# SD_Card.net
KiCad netlist of a schematic drawn in Altium Designer
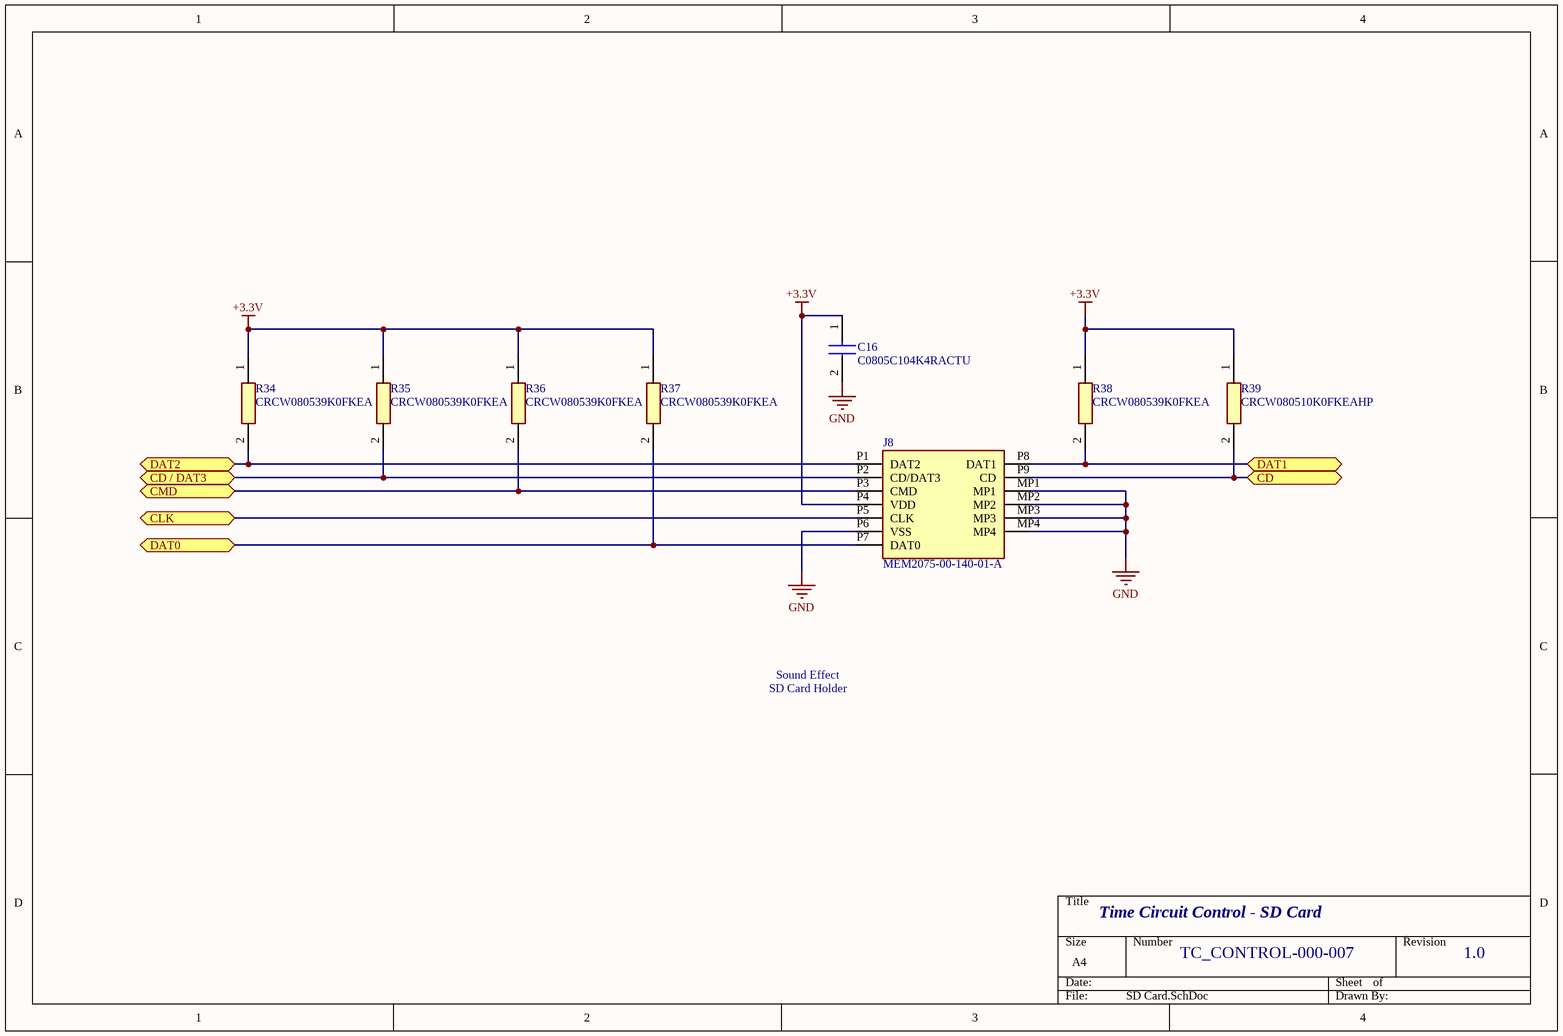
[diagram p0: SD Card.SchDoc]

(export (version "E")
  (design (tool "Eeschema 10.0.6"))
  (components
    (comp (ref "C16")
      (value "C0805C104K4RACTU")
      (footprint "SamacSys:CAPC2012X88N")
      (description "Capacitor")
      (fields (field (name "MOUSER PART NUMBER") "80-C0805C104K4R"))
      (libsource (lib "SamacSys") (part "C0805C104K4RACTU"))
    )
    (comp (ref "J8")
      (value "MEM2075-00-140-01-A")
      (footprint "SamacSys:MEM20750014001A")
      (description "Connector")
      (fields (field (name "MOUSER PART NUMBER") "640-MEM20750014001A"))
      (libsource (lib "SamacSys") (part "MEM2075-00-140-01-A"))
    )
    (comp (ref "R34")
      (value "CRCW080539K0FKEA")
      (footprint "SamacSys:RESC2012X50N")
      (description "Resistor")
      (fields (field (name "MOUSER PART NUMBER") "71-CRCW080539K0FKEA"))
      (libsource (lib "SamacSys") (part "CRCW080539K0FKEA"))
    )
    (comp (ref "R35")
      (value "CRCW080539K0FKEA")
      (footprint "SamacSys:RESC2012X50N")
      (description "Resistor")
      (fields (field (name "MOUSER PART NUMBER") "71-CRCW080539K0FKEA"))
      (libsource (lib "SamacSys") (part "CRCW080539K0FKEA"))
    )
    (comp (ref "R36")
      (value "CRCW080539K0FKEA")
      (footprint "SamacSys:RESC2012X50N")
      (description "Resistor")
      (fields (field (name "MOUSER PART NUMBER") "71-CRCW080539K0FKEA"))
      (libsource (lib "SamacSys") (part "CRCW080539K0FKEA"))
    )
    (comp (ref "R37")
      (value "CRCW080539K0FKEA")
      (footprint "SamacSys:RESC2012X50N")
      (description "Resistor")
      (fields (field (name "MOUSER PART NUMBER") "71-CRCW080539K0FKEA"))
      (libsource (lib "SamacSys") (part "CRCW080539K0FKEA"))
    )
    (comp (ref "R38")
      (value "CRCW080539K0FKEA")
      (footprint "SamacSys:RESC2012X50N")
      (description "Resistor")
      (fields (field (name "MOUSER PART NUMBER") "71-CRCW080539K0FKEA"))
      (libsource (lib "SamacSys") (part "CRCW080539K0FKEA"))
    )
    (comp (ref "R39")
      (value "CRCW080510K0FKEAHP")
      (footprint "SamacSys:RESC2012X60N")
      (description "Resistor")
      (fields (field (name "MOUSER PART NUMBER") "71-CRCW080510K0FKEAH"))
      (libsource (lib "SamacSys") (part "CRCW080510K0FKEAHP"))
    )
  )
  (nets
    (net (code "1") (name "+3.3V") (class "Default")
      (node (ref "C16") (pin "1") (pinfunction "1_1") (pintype "passive"))
      (node (ref "J8") (pin "P4") (pinfunction "VDD_P4") (pintype "passive"))
      (node (ref "R34") (pin "1") (pinfunction "1_1") (pintype "passive"))
      (node (ref "R35") (pin "1") (pinfunction "1_1") (pintype "passive"))
      (node (ref "R36") (pin "1") (pinfunction "1_1") (pintype "passive"))
      (node (ref "R37") (pin "1") (pinfunction "1_1") (pintype "passive"))
      (node (ref "R38") (pin "1") (pinfunction "1_1") (pintype "passive"))
      (node (ref "R39") (pin "1") (pinfunction "1_1") (pintype "passive"))
    )
    (net (code "2") (name "/CD") (class "Default")
      (node (ref "J8") (pin "P9") (pinfunction "CD_P9") (pintype "passive"))
      (node (ref "R39") (pin "2") (pinfunction "2_2") (pintype "passive"))
    )
    (net (code "3") (name "/CD {slash} DAT3") (class "Default")
      (node (ref "J8") (pin "P2") (pinfunction "CD/DAT3_P2") (pintype "passive"))
      (node (ref "R35") (pin "2") (pinfunction "2_2") (pintype "passive"))
    )
    (net (code "4") (name "/CLK") (class "Default")
      (node (ref "J8") (pin "P5") (pinfunction "CLK_P5") (pintype "passive"))
    )
    (net (code "5") (name "/CMD") (class "Default")
      (node (ref "J8") (pin "P3") (pinfunction "CMD_P3") (pintype "passive"))
      (node (ref "R36") (pin "2") (pinfunction "2_2") (pintype "passive"))
    )
    (net (code "6") (name "/DAT0") (class "Default")
      (node (ref "J8") (pin "P7") (pinfunction "DAT0_P7") (pintype "passive"))
      (node (ref "R37") (pin "2") (pinfunction "2_2") (pintype "passive"))
    )
    (net (code "7") (name "/DAT1") (class "Default")
      (node (ref "J8") (pin "P8") (pinfunction "DAT1_P8") (pintype "passive"))
      (node (ref "R38") (pin "2") (pinfunction "2_2") (pintype "passive"))
    )
    (net (code "8") (name "/DAT2") (class "Default")
      (node (ref "J8") (pin "P1") (pinfunction "DAT2_P1") (pintype "passive"))
      (node (ref "R34") (pin "2") (pinfunction "2_2") (pintype "passive"))
    )
    (net (code "9") (name "GND") (class "Default")
      (node (ref "C16") (pin "2") (pinfunction "2_2") (pintype "passive"))
      (node (ref "J8") (pin "MP1") (pinfunction "MP1_MP1") (pintype "passive"))
      (node (ref "J8") (pin "MP2") (pinfunction "MP2_MP2") (pintype "passive"))
      (node (ref "J8") (pin "MP3") (pinfunction "MP3_MP3") (pintype "passive"))
      (node (ref "J8") (pin "MP4") (pinfunction "MP4_MP4") (pintype "passive"))
      (node (ref "J8") (pin "P6") (pinfunction "VSS_P6") (pintype "passive"))
    )
  )
)
